# TopLevel.net
KiCad netlist of a schematic drawn in Altium Designer
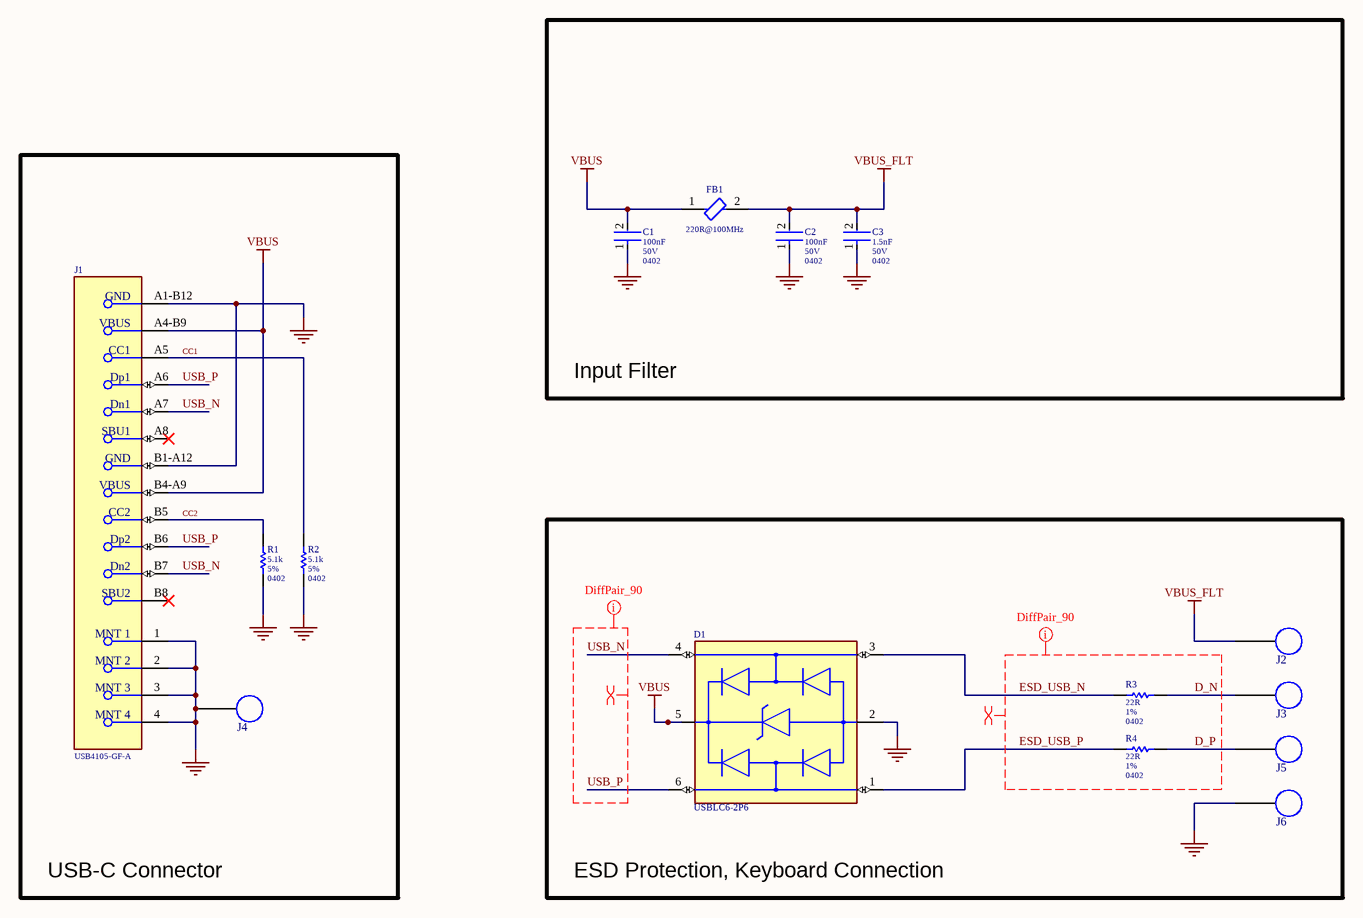
[diagram p0: TopLevel.SchDoc]

(export (version "E")
  (design (tool "Eeschema 10.0.6"))
  (components
    (comp (ref "C1")
      (value "100nF")
      (footprint "0402")
      (description "Multi-Layer Ceramic Capacitor 100nF 50V X7R ±10% 0402 Paper T/R")
      (fields
        (field (name "TOLERANCE") "10%")
        (field (name "VOLTAGE") "50V")
        (field (name "MANUFACTURER") "Murata")
      )
      (libsource (lib "Altium Content Vault") (part "02cd4be3c70576c341d710602a673aa"))
    )
    (comp (ref "C2")
      (value "100nF")
      (footprint "0402")
      (description "Multi-Layer Ceramic Capacitor 100nF 50V X7R ±10% 0402 Paper T/R")
      (fields
        (field (name "TOLERANCE") "10%")
        (field (name "VOLTAGE") "50V")
        (field (name "MANUFACTURER") "Murata")
      )
      (libsource (lib "Altium Content Vault") (part "02cd4be3c70576c341d710602a673aa"))
    )
    (comp (ref "C3")
      (value "1.5nF")
      (footprint "0402")
      (description "Multi-Layer Ceramic Capacitor 1.5nF 50V X7R ±10% 0402 Paper T/R")
      (fields
        (field (name "TOLERANCE") "10%")
        (field (name "VOLTAGE") "50V")
        (field (name "MANUFACTURER") "Murata")
      )
      (libsource (lib "Altium Content Vault") (part "02cd4be3c70576c341d710602a673aa"))
    )
    (comp (ref "D1")
      (value "USBLC6-2P6")
      (footprint "FP-SOT-666-MFG")
      (description "TVS DIODE 5.25V 17V SOT666")
      (libsource (lib "Altium Content Vault") (part "c871e55f7e3243d341edbd671b98d92"))
    )
    (comp (ref "FB1")
      (value "BLM18PG221SN1D")
      (footprint "FP-BLM18-0_15-t0_8-IPC_B")
      (description "Chip Ferrite Bead, 0603, 220Ω @ 100MHz, 0.1Ω, 25%, 1.4A")
      (fields
        (field (name "ESR (EQUIVALENT SERIES RESISTANCE)") "220R@100MHz")
        (field (name "TOLERANCE") "25%")
      )
      (libsource (lib "Altium Content Vault") (part "5f30dd21d616792df468990f7003faa"))
    )
    (comp (ref "J1")
      (value "USB4105-GF-A")
      (footprint "FP-USB4105-GF-A-MFG")
      (description "CONN RCPT USB2.0 TYPEC 5A")
      (fields
        (field (name "MANUFACTURER") "GCT")
        (field (name "OCTOPART") "https://octopart.com/usb4105-gf-a-gct-106627878")
      )
      (libsource (lib "Altium Content Vault") (part "e7c17a616881a82b79941196b4bec10"))
    )
    (comp (ref "J2")
      (value "20AWG_WTB_TH")
      (footprint "20AWG_WTB_TH")
      (description "20AWG Wire to Board Through Hole")
      (libsource (lib "000169(Quick_Fire_TK_USBC)") (part "20AWG_WTB_TH"))
    )
    (comp (ref "J3")
      (value "26AWG_WTB_TH")
      (footprint "26AWG_WTB_TH")
      (description "26AWG Wire to Board Through Hole")
      (libsource (lib "000169(Quick_Fire_TK_USBC)") (part "26AWG_WTB_TH"))
    )
    (comp (ref "J4")
      (value "20AWG_WTB_TH")
      (footprint "20AWG_WTB_TH")
      (description "20AWG Wire to Board Through Hole")
      (libsource (lib "000169(Quick_Fire_TK_USBC)") (part "20AWG_WTB_TH"))
    )
    (comp (ref "J5")
      (value "26AWG_WTB_TH")
      (footprint "26AWG_WTB_TH")
      (description "26AWG Wire to Board Through Hole")
      (libsource (lib "000169(Quick_Fire_TK_USBC)") (part "26AWG_WTB_TH"))
    )
    (comp (ref "J6")
      (value "20AWG_WTB_TH")
      (footprint "20AWG_WTB_TH")
      (description "20AWG Wire to Board Through Hole")
      (libsource (lib "000169(Quick_Fire_TK_USBC)") (part "20AWG_WTB_TH"))
    )
    (comp (ref "R1")
      (value "5.1k")
      (footprint "0402")
      (description "Thick Film Resistors - SMD 5.1 kOhms 62.5mW 0402 5%")
      (fields
        (field (name "MANUFACTURER") "Yageo / Phycomp")
        (field (name "PART NUMBER") "RC0402JR-075K1L")
        (field (name "TOLERANCE") "5%")
      )
      (libsource (lib "Altium Content Vault") (part "RES"))
    )
    (comp (ref "R2")
      (value "5.1k")
      (footprint "0402")
      (description "Thick Film Resistors - SMD 5.1 kOhms 62.5mW 0402 5%")
      (fields
        (field (name "MANUFACTURER") "Yageo / Phycomp")
        (field (name "PART NUMBER") "RC0402JR-075K1L")
        (field (name "TOLERANCE") "5%")
      )
      (libsource (lib "Altium Content Vault") (part "RES"))
    )
    (comp (ref "R3")
      (value "22R")
      (footprint "0402")
      (description "Thick Film Resistors 22 Ohms 62.5mW 0402 1%")
      (fields
        (field (name "MANUFACTURER") "Yageo / Phycomp")
        (field (name "PART NUMBER") "RC0402FR-0722RL")
        (field (name "TOLERANCE") "1%")
      )
      (libsource (lib "Altium Content Vault") (part "RES"))
    )
    (comp (ref "R4")
      (value "22R")
      (footprint "0402")
      (description "Thick Film Resistors 22 Ohms 62.5mW 0402 1%")
      (fields
        (field (name "MANUFACTURER") "Yageo / Phycomp")
        (field (name "PART NUMBER") "RC0402FR-0722RL")
        (field (name "TOLERANCE") "1%")
      )
      (libsource (lib "Altium Content Vault") (part "RES"))
    )
  )
  (nets
    (net (code "1") (name "/CC1") (class "Default")
      (node (ref "J1") (pin "A5") (pinfunction "CC1_A5") (pintype "power_in"))
      (node (ref "R2") (pin "2") (pinfunction "2_2") (pintype "passive"))
    )
    (net (code "2") (name "/CC2") (class "Default")
      (node (ref "J1") (pin "B5") (pinfunction "CC2_B5") (pintype "bidirectional"))
      (node (ref "R1") (pin "2") (pinfunction "2_2") (pintype "passive"))
    )
    (net (code "3") (name "/D_N") (class "Default")
      (node (ref "J3") (pin "1") (pinfunction "PIN_1") (pintype "passive"))
      (node (ref "R3") (pin "2") (pinfunction "2_2") (pintype "passive"))
    )
    (net (code "4") (name "/D_P") (class "Default")
      (node (ref "J5") (pin "1") (pinfunction "PIN_1") (pintype "passive"))
      (node (ref "R4") (pin "2") (pinfunction "2_2") (pintype "passive"))
    )
    (net (code "5") (name "/ESD_USB_N") (class "Default")
      (node (ref "D1") (pin "3") (pinfunction "I/O2_3") (pintype "bidirectional"))
      (node (ref "R3") (pin "1") (pinfunction "1_1") (pintype "passive"))
    )
    (net (code "6") (name "/ESD_USB_P") (class "Default")
      (node (ref "D1") (pin "1") (pinfunction "I/O1_1") (pintype "bidirectional"))
      (node (ref "R4") (pin "1") (pinfunction "1_1") (pintype "passive"))
    )
    (net (code "7") (name "/USB_N") (class "Default")
      (node (ref "D1") (pin "4") (pinfunction "I/O2_4") (pintype "bidirectional"))
      (node (ref "J1") (pin "A7") (pinfunction "Dn1_A7") (pintype "bidirectional"))
      (node (ref "J1") (pin "B7") (pinfunction "Dn2_B7") (pintype "bidirectional"))
    )
    (net (code "8") (name "/USB_P") (class "Default")
      (node (ref "D1") (pin "6") (pinfunction "I/O1_6") (pintype "bidirectional"))
      (node (ref "J1") (pin "A6") (pinfunction "Dp1_A6") (pintype "bidirectional"))
      (node (ref "J1") (pin "B6") (pinfunction "Dp2_B6") (pintype "bidirectional"))
    )
    (net (code "9") (name "GND") (class "Default")
      (node (ref "C1") (pin "1") (pinfunction "1_1") (pintype "passive"))
      (node (ref "C2") (pin "1") (pinfunction "1_1") (pintype "passive"))
      (node (ref "C3") (pin "1") (pinfunction "1_1") (pintype "passive"))
      (node (ref "D1") (pin "2") (pinfunction "GND_2") (pintype "power_in"))
      (node (ref "J1") (pin "1") (pinfunction "MNT_1_1") (pintype "power_in"))
      (node (ref "J1") (pin "2") (pinfunction "MNT_2_2") (pintype "power_in"))
      (node (ref "J1") (pin "3") (pinfunction "MNT_3_3") (pintype "power_in"))
      (node (ref "J1") (pin "4") (pinfunction "MNT_4_4") (pintype "power_in"))
      (node (ref "J1") (pin "A1-B12") (pinfunction "GND_A1-B12") (pintype "power_in"))
      (node (ref "J1") (pin "B1-A12") (pinfunction "GND_B1-A12") (pintype "bidirectional"))
      (node (ref "J4") (pin "1") (pinfunction "PIN_1") (pintype "passive"))
      (node (ref "J6") (pin "1") (pinfunction "PIN_1") (pintype "passive"))
      (node (ref "R1") (pin "1") (pinfunction "1_1") (pintype "passive"))
      (node (ref "R2") (pin "1") (pinfunction "1_1") (pintype "passive"))
    )
    (net (code "10") (name "VBUS") (class "Default")
      (node (ref "C1") (pin "2") (pinfunction "2_2") (pintype "passive"))
      (node (ref "D1") (pin "5") (pinfunction "VBUS_5") (pintype "power_in"))
      (node (ref "FB1") (pin "1") (pinfunction "1_1") (pintype "passive"))
      (node (ref "J1") (pin "A4-B9") (pinfunction "VBUS_A4-B9") (pintype "power_in"))
      (node (ref "J1") (pin "B4-A9") (pinfunction "VBUS_B4-A9") (pintype "bidirectional"))
    )
    (net (code "11") (name "VBUS_FLT") (class "Default")
      (node (ref "C2") (pin "2") (pinfunction "2_2") (pintype "passive"))
      (node (ref "C3") (pin "2") (pinfunction "2_2") (pintype "passive"))
      (node (ref "FB1") (pin "2") (pinfunction "2_2") (pintype "passive"))
      (node (ref "J2") (pin "1") (pinfunction "PIN_1") (pintype "passive"))
    )
    (net (code "12") (name "unconnected-(J1-SBU1-PadA8)") (class "Default")
      (node (ref "J1") (pin "A8") (pinfunction "SBU1_A8") (pintype "bidirectional+no_connect"))
    )
    (net (code "13") (name "unconnected-(J1-SBU2-PadB8)") (class "Default")
      (node (ref "J1") (pin "B8") (pinfunction "SBU2_B8") (pintype "power_in+no_connect"))
    )
  )
)
